# Koala_Bear.net
KiCad netlist of a schematic drawn in EAGLE
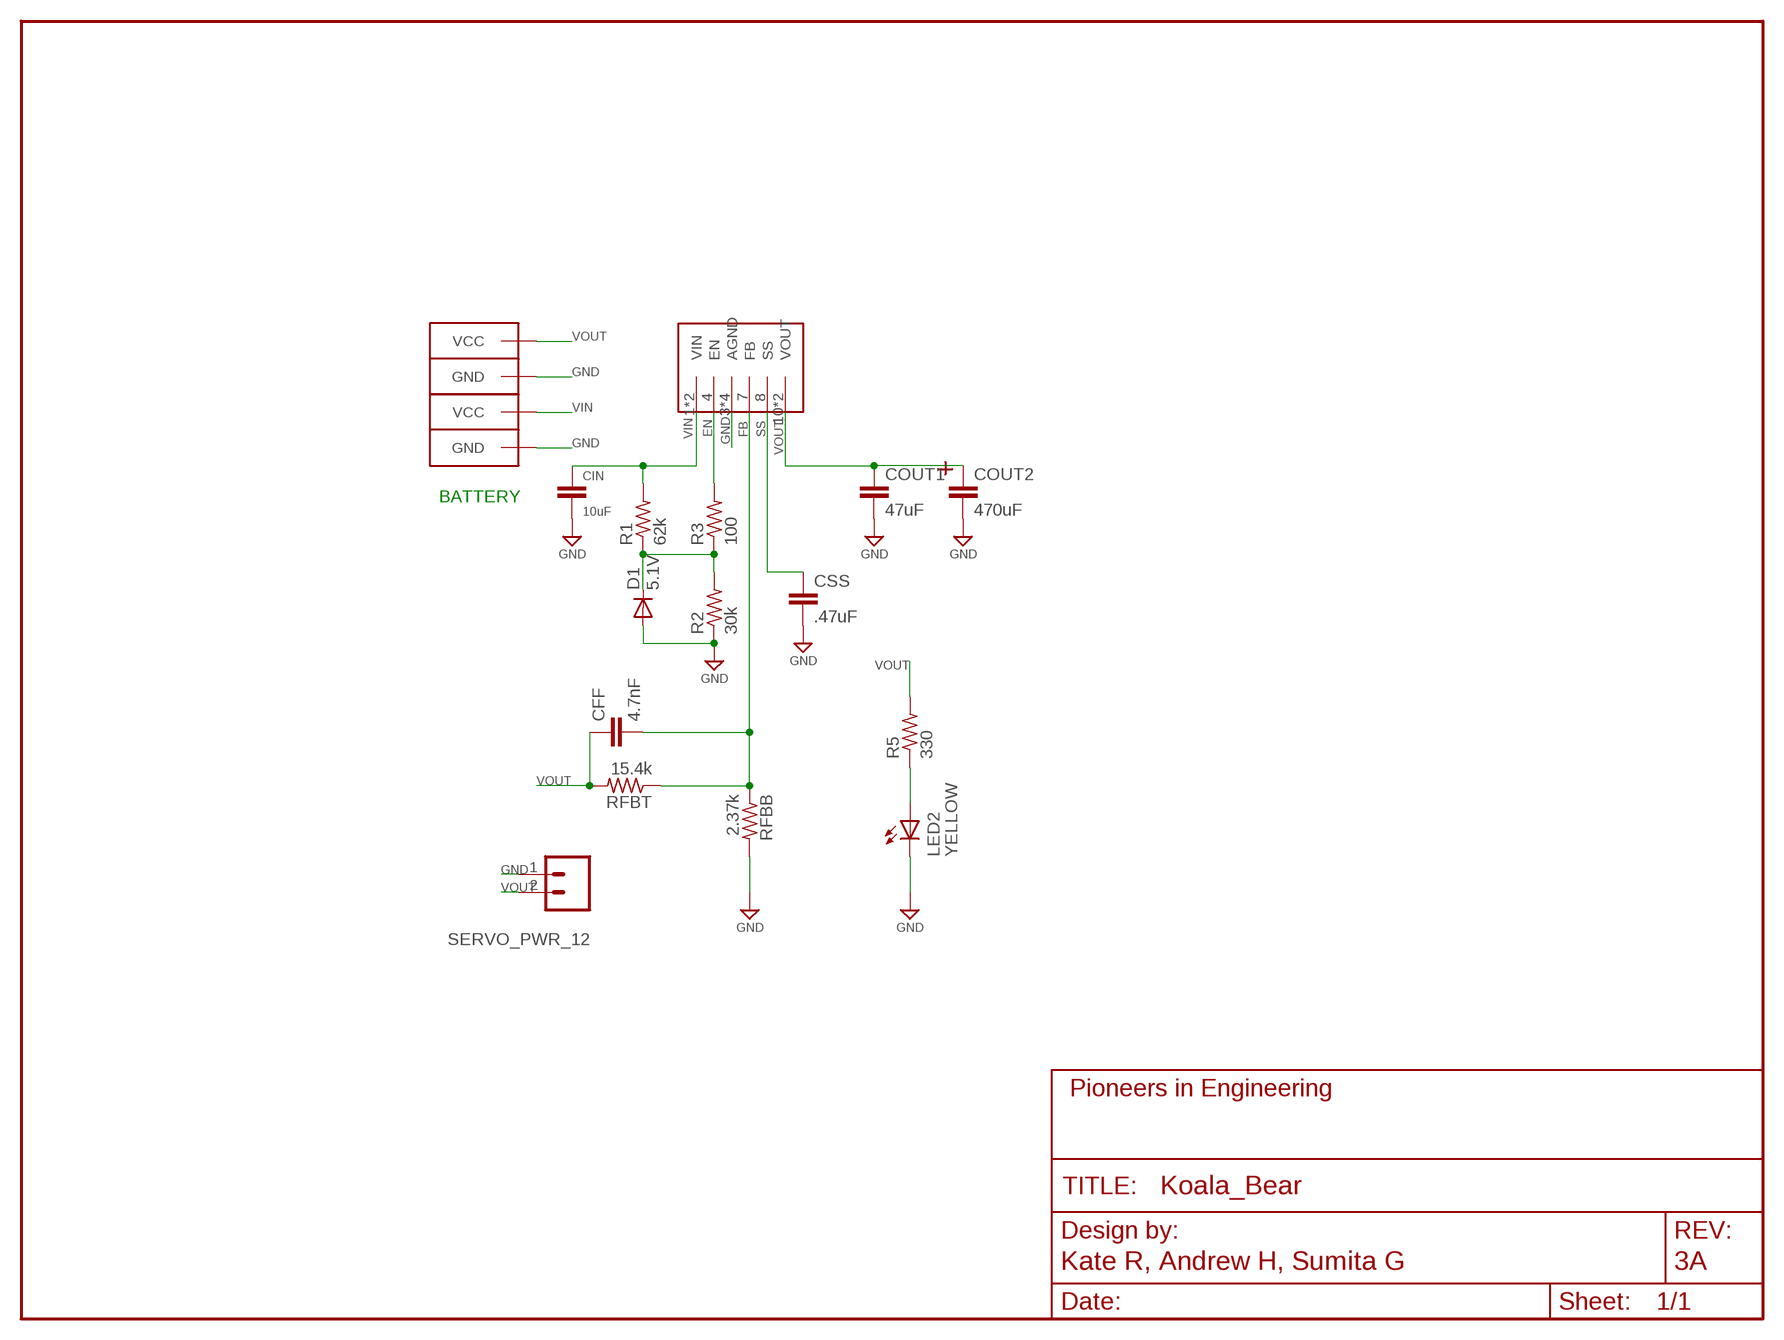
[diagram p0: schematic, sheet 1]

(export (version "E")
  (design (tool "Eeschema 10.0.6"))
  (components
    (comp (ref "CFF")
      (value "4.7nF")
      (footprint "eagle-import:0603-CAP")
      (libsource (lib "eagle-import") (part "CAP0603-CAP"))
    )
    (comp (ref "CIN")
      (value "10uF")
      (footprint "eagle-import:1206")
      (libsource (lib "eagle-import") (part "CAP1206"))
    )
    (comp (ref "COUT1")
      (value "47uF")
      (footprint "eagle-import:1206")
      (libsource (lib "eagle-import") (part "CAP1206"))
    )
    (comp (ref "COUT2")
      (value "470uF")
      (footprint "eagle-import:TANT_CASE_E")
      (libsource (lib "eagle-import") (part "TANT_CASE_E"))
    )
    (comp (ref "CSS")
      (value ".47uF")
      (footprint "eagle-import:0603-CAP")
      (libsource (lib "eagle-import") (part "CAP0603-CAP"))
    )
    (comp (ref "D1")
      (value "5.1V")
      (footprint "eagle-import:SOD-323")
      (libsource (lib "eagle-import") (part "DIODESOD-323"))
    )
    (comp (ref "LED2")
      (value "YELLOW")
      (footprint "eagle-import:LED-0805")
      (libsource (lib "eagle-import") (part "LED0805"))
    )
    (comp (ref "PWR")
      (value "ANDERSONVERTICAL")
      (footprint "eagle-import:ANDERSON_VERTICAL")
      (libsource (lib "eagle-import") (part "ANDERSONVERTICAL"))
    )
    (comp (ref "PWR1")
      (value "ANDERSONVERTICAL")
      (footprint "eagle-import:ANDERSON_VERTICAL")
      (libsource (lib "eagle-import") (part "ANDERSONVERTICAL"))
    )
    (comp (ref "R1")
      (value "62k")
      (footprint "eagle-import:R0603")
      (libsource (lib "eagle-import") (part "R-US_R0603"))
    )
    (comp (ref "R2")
      (value "30k")
      (footprint "eagle-import:R0603")
      (libsource (lib "eagle-import") (part "R-US_R0603"))
    )
    (comp (ref "R3")
      (value "100")
      (footprint "eagle-import:R0603")
      (libsource (lib "eagle-import") (part "R-US_R0603"))
    )
    (comp (ref "R5")
      (value "330")
      (footprint "eagle-import:R0603")
      (libsource (lib "eagle-import") (part "R-US_R0603"))
    )
    (comp (ref "RFBB")
      (value "2.37k")
      (footprint "eagle-import:R0603")
      (libsource (lib "eagle-import") (part "R-US_R0603"))
    )
    (comp (ref "RFBT")
      (value "15.4k")
      (footprint "eagle-import:R0603")
      (libsource (lib "eagle-import") (part "R-US_R0603"))
    )
    (comp (ref "SERVO_PWR_12")
      (value "M02PTH")
      (footprint "eagle-import:1X02")
      (libsource (lib "eagle-import") (part "M02PTH"))
    )
    (comp (ref "U$1")
      (value "LMZ12010")
      (footprint "eagle-import:LMZ12010")
      (libsource (lib "eagle-import") (part "LMZ12010"))
    )
  )
  (nets
    (net (code "1") (name "/EN") (class "Default")
      (node (ref "R3") (pin "2") (pinfunction "2_2") (pintype "passive"))
      (node (ref "U$1") (pin "4") (pinfunction "EN_4") (pintype "bidirectional"))
    )
    (net (code "2") (name "/FB") (class "Default")
      (node (ref "CFF") (pin "2") (pinfunction "2_2") (pintype "passive"))
      (node (ref "RFBB") (pin "1") (pinfunction "1_1") (pintype "passive"))
      (node (ref "RFBT") (pin "1") (pinfunction "1_1") (pintype "passive"))
      (node (ref "U$1") (pin "7") (pinfunction "FB_7") (pintype "bidirectional"))
    )
    (net (code "3") (name "/SS") (class "Default")
      (node (ref "CSS") (pin "1") (pinfunction "1_1") (pintype "passive"))
      (node (ref "U$1") (pin "8") (pinfunction "SS_8") (pintype "bidirectional"))
    )
    (net (code "4") (name "/VIN") (class "Default")
      (node (ref "CIN") (pin "1") (pinfunction "1_1") (pintype "passive"))
      (node (ref "PWR") (pin "PIN2") (pinfunction "VCC_PIN2") (pintype "bidirectional"))
      (node (ref "R1") (pin "2") (pinfunction "2_2") (pintype "passive"))
      (node (ref "U$1") (pin "1") (pinfunction "VIN_1") (pintype "bidirectional"))
      (node (ref "U$1") (pin "2") (pinfunction "VIN_2") (pintype "bidirectional"))
    )
    (net (code "5") (name "/VOUT") (class "Default")
      (node (ref "CFF") (pin "1") (pinfunction "1_1") (pintype "passive"))
      (node (ref "COUT1") (pin "1") (pinfunction "1_1") (pintype "passive"))
      (node (ref "COUT2") (pin "POS") (pinfunction "POS_POS") (pintype "passive"))
      (node (ref "PWR1") (pin "PIN2") (pinfunction "VCC_PIN2") (pintype "bidirectional"))
      (node (ref "R5") (pin "2") (pinfunction "2_2") (pintype "passive"))
      (node (ref "RFBT") (pin "2") (pinfunction "2_2") (pintype "passive"))
      (node (ref "SERVO_PWR_12") (pin "2") (pinfunction "2_2") (pintype "passive"))
      (node (ref "U$1") (pin "10") (pinfunction "VOUT_10") (pintype "bidirectional"))
      (node (ref "U$1") (pin "11") (pinfunction "VOUT_11") (pintype "bidirectional"))
    )
    (net (code "6") (name "GND") (class "Default")
      (node (ref "CIN") (pin "2") (pinfunction "2_2") (pintype "passive"))
      (node (ref "COUT1") (pin "2") (pinfunction "2_2") (pintype "passive"))
      (node (ref "COUT2") (pin "NEG") (pinfunction "NEG_NEG") (pintype "passive"))
      (node (ref "CSS") (pin "2") (pinfunction "2_2") (pintype "passive"))
      (node (ref "D1") (pin "1") (pinfunction "A_1") (pintype "passive"))
      (node (ref "LED2") (pin "C") (pinfunction "C_C") (pintype "passive"))
      (node (ref "PWR") (pin "PIN1") (pinfunction "GND_PIN1") (pintype "bidirectional"))
      (node (ref "PWR1") (pin "PIN1") (pinfunction "GND_PIN1") (pintype "bidirectional"))
      (node (ref "R2") (pin "1") (pinfunction "1_1") (pintype "passive"))
      (node (ref "RFBB") (pin "2") (pinfunction "2_2") (pintype "passive"))
      (node (ref "SERVO_PWR_12") (pin "1") (pinfunction "1_1") (pintype "passive"))
      (node (ref "U$1") (pin "3") (pinfunction "AGND_3") (pintype "bidirectional"))
      (node (ref "U$1") (pin "5") (pinfunction "AGND_5") (pintype "bidirectional"))
      (node (ref "U$1") (pin "6") (pinfunction "AGND_6") (pintype "bidirectional"))
      (node (ref "U$1") (pin "GND") (pinfunction "AGND_GND") (pintype "bidirectional"))
    )
    (net (code "7") (name "Net-(D1-C)") (class "Default")
      (node (ref "D1") (pin "2") (pinfunction "C_2") (pintype "passive"))
      (node (ref "R1") (pin "1") (pinfunction "1_1") (pintype "passive"))
      (node (ref "R2") (pin "2") (pinfunction "2_2") (pintype "passive"))
      (node (ref "R3") (pin "1") (pinfunction "1_1") (pintype "passive"))
    )
    (net (code "8") (name "Net-(LED2-PadA)") (class "Default")
      (node (ref "LED2") (pin "A") (pinfunction "A_A") (pintype "passive"))
      (node (ref "R5") (pin "1") (pinfunction "1_1") (pintype "passive"))
    )
  )
)
